# 1_MC_Peripherals.net
KiCad netlist of a schematic drawn in Altium Designer
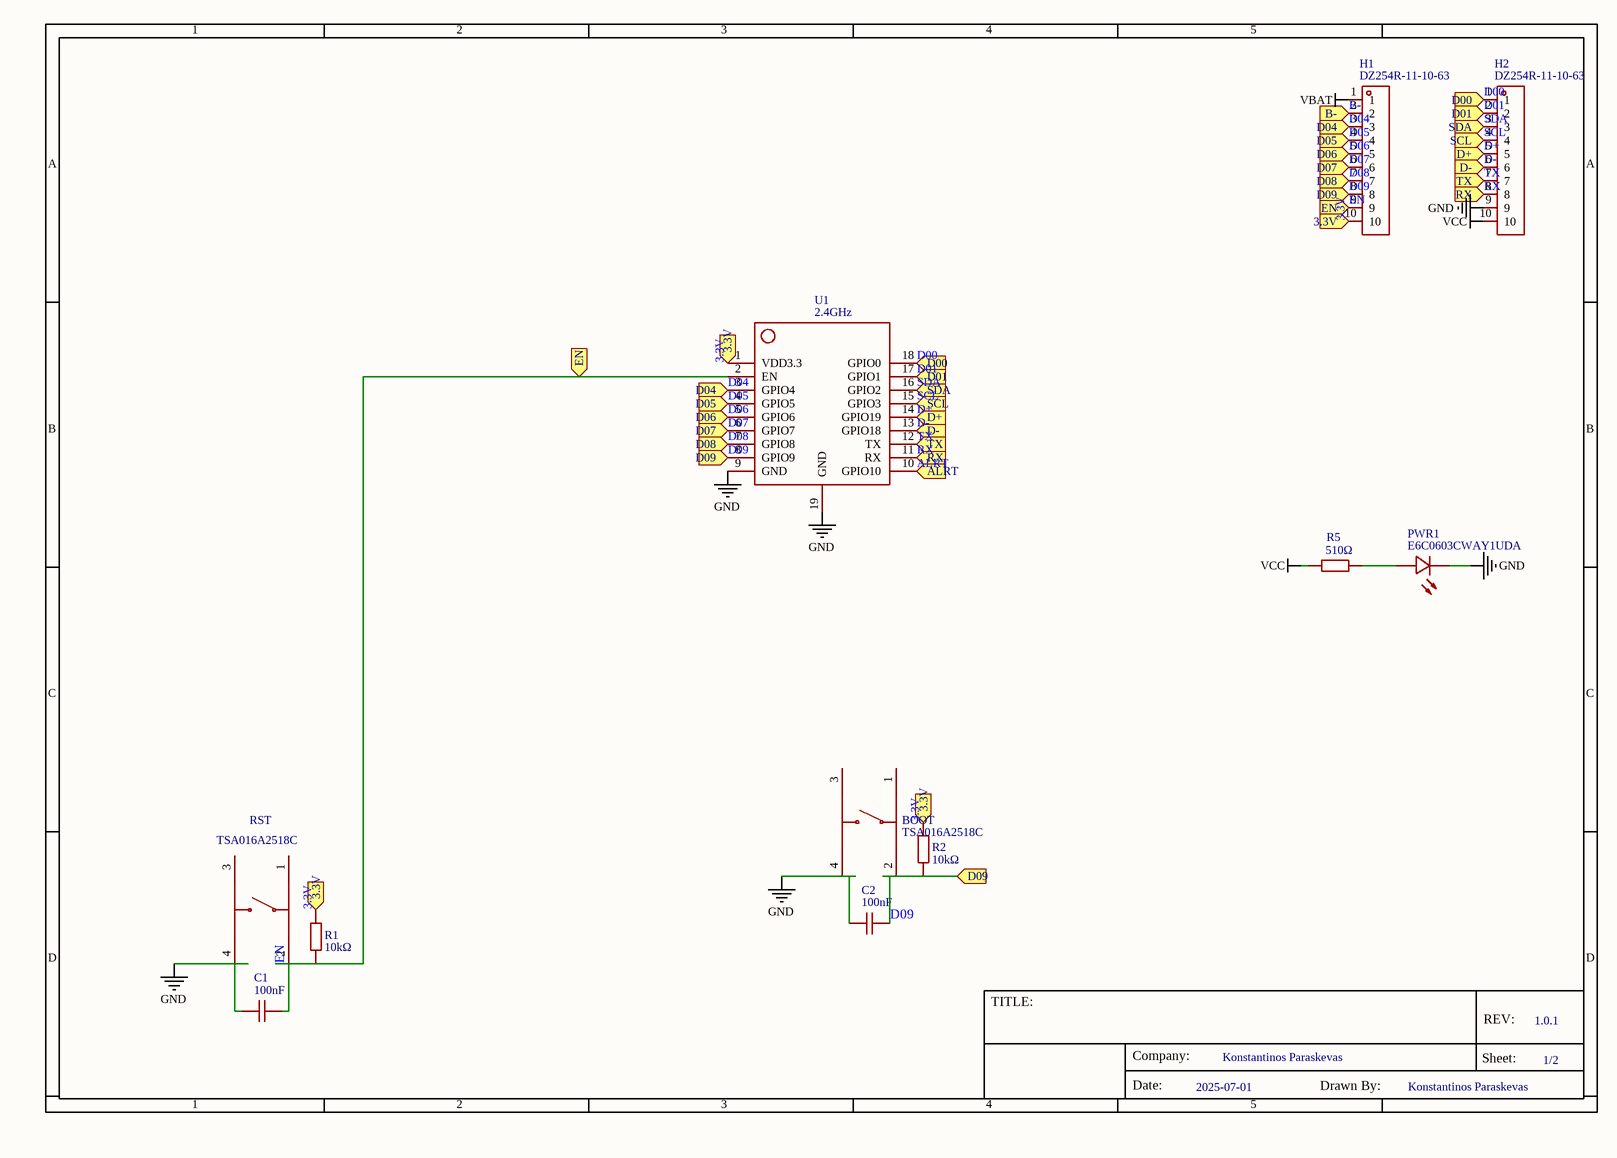
[diagram p0: 1_MC & Peripherals.schdoc]

(export (version "E")
  (design (tool "Eeschema 10.0.6"))
  (components
    (comp (ref "BOOT")
      (value "TSA016A2518C")
      (footprint "SW-SMD_4P-L4.2-W3.3-P2.15-LS4.6")
      (fields (field (name "MANUFACTURER") "BZCN(博众电气)"))
      (libsource (lib "altium-import") (part "root_3_TSA016A2518C_"))
    )
    (comp (ref "C1")
      (value "100nF")
      (footprint "C0402")
      (fields
        (field (name "MANUFACTURER") "FH(风华)")
        (field (name "MANUFACTURER PART") "0402B104K160NT")
        (field (name "TOLERANCE") "±10%")
      )
      (libsource (lib "altium-import") (part "root_0_0402B104K160NT_"))
    )
    (comp (ref "C2")
      (value "100nF")
      (footprint "C0402")
      (fields
        (field (name "MANUFACTURER") "FH(风华)")
        (field (name "MANUFACTURER PART") "0402B104K160NT")
        (field (name "TOLERANCE") "±10%")
      )
      (libsource (lib "altium-import") (part "root_0_0402B104K160NT_"))
    )
    (comp (ref "H1")
      (value "DZ254R-11-10-63")
      (footprint "HDR-TH_10P-P2.54-V-M")
      (fields (field (name "MANUFACTURER") "DEALON(德艺隆)"))
      (libsource (lib "altium-import") (part "root_0_DZ254R-11-10-63_"))
    )
    (comp (ref "H2")
      (value "DZ254R-11-10-63")
      (footprint "HDR-TH_10P-P2.54-V-M")
      (fields (field (name "MANUFACTURER") "DEALON(德艺隆)"))
      (libsource (lib "altium-import") (part "root_0_DZ254R-11-10-63_"))
    )
    (comp (ref "PWR1")
      (value "E6C0603CWAY1UDA")
      (footprint "LED0603-R-RD_WHITE")
      (fields (field (name "MANUFACTURER") "ekinglux(亿晶源)"))
      (libsource (lib "altium-import") (part "root_2_E6C0603CWAY1UDA_"))
    )
    (comp (ref "R1")
      (value "10kΩ")
      (footprint "R0402")
      (fields
        (field (name "MANUFACTURER") "大毅科技")
        (field (name "MANUFACTURER PART") "RMS04FT1002")
        (field (name "TOLERANCE") "±1%")
      )
      (libsource (lib "altium-import") (part "root_1_RMS04FT1002_"))
    )
    (comp (ref "R2")
      (value "10kΩ")
      (footprint "R0402")
      (fields
        (field (name "MANUFACTURER") "大毅科技")
        (field (name "MANUFACTURER PART") "RMS04FT1002")
        (field (name "TOLERANCE") "±1%")
      )
      (libsource (lib "altium-import") (part "root_1_RMS04FT1002_"))
    )
    (comp (ref "R5")
      (value "510Ω")
      (footprint "R0402")
      (fields
        (field (name "MANUFACTURER") "UNI-ROYAL(厚声)")
        (field (name "MANUFACTURER PART") "0402WGF5100TCE")
        (field (name "TOLERANCE") "±1%")
      )
      (libsource (lib "altium-import") (part "root_0_0402WGF5100TCE_"))
    )
    (comp (ref "RST")
      (value "TSA016A2518C")
      (footprint "SW-SMD_4P-L4.2-W3.3-P2.15-LS4.6")
      (fields (field (name "MANUFACTURER") "BZCN(博众电气)"))
      (libsource (lib "altium-import") (part "root_3_TSA016A2518C_"))
    )
    (comp (ref "U1")
      (value "2.4GHz")
      (footprint "BULETM-SMD_ESPRESSIF_ESP32-C3-WROOM-02-N4-4MB")
      (fields
        (field (name "MANUFACTURER") "ESPRESSIF(乐鑫)")
        (field (name "MANUFACTURER PART") "ESP32-C3-WROOM-02-N4")
      )
      (libsource (lib "altium-import") (part "root_0_ESP32-C3-WROOM-02-N4_C2934560_"))
    )
  )
  (nets
    (net (code "1") (name "/3.3V") (class "Default")
      (node (ref "H1") (pin "10") (pinfunction "10_10") (pintype "passive"))
      (node (ref "R1") (pin "2") (pinfunction "2_2") (pintype "passive"))
      (node (ref "R2") (pin "2") (pinfunction "2_2") (pintype "passive"))
      (node (ref "U1") (pin "1") (pinfunction "VDD3.3_1") (pintype "passive"))
    )
    (net (code "2") (name "/ALRT") (class "Default")
      (node (ref "U1") (pin "10") (pinfunction "GPIO10_10") (pintype "passive"))
    )
    (net (code "3") (name "/B-") (class "Default")
      (node (ref "H1") (pin "2") (pinfunction "2_2") (pintype "passive"))
    )
    (net (code "4") (name "/D+") (class "Default")
      (node (ref "H2") (pin "5") (pinfunction "5_5") (pintype "passive"))
      (node (ref "U1") (pin "14") (pinfunction "GPIO19_14") (pintype "passive"))
    )
    (net (code "5") (name "/D-") (class "Default")
      (node (ref "H2") (pin "6") (pinfunction "6_6") (pintype "passive"))
      (node (ref "U1") (pin "13") (pinfunction "GPIO18_13") (pintype "passive"))
    )
    (net (code "6") (name "/D00") (class "Default")
      (node (ref "H2") (pin "1") (pinfunction "1_1") (pintype "passive"))
      (node (ref "U1") (pin "18") (pinfunction "GPIO0_18") (pintype "passive"))
    )
    (net (code "7") (name "/D01") (class "Default")
      (node (ref "H2") (pin "2") (pinfunction "2_2") (pintype "passive"))
      (node (ref "U1") (pin "17") (pinfunction "GPIO1_17") (pintype "passive"))
    )
    (net (code "8") (name "/D04") (class "Default")
      (node (ref "H1") (pin "3") (pinfunction "3_3") (pintype "passive"))
      (node (ref "U1") (pin "3") (pinfunction "GPIO4_3") (pintype "passive"))
    )
    (net (code "9") (name "/D05") (class "Default")
      (node (ref "H1") (pin "4") (pinfunction "4_4") (pintype "passive"))
      (node (ref "U1") (pin "4") (pinfunction "GPIO5_4") (pintype "passive"))
    )
    (net (code "10") (name "/D06") (class "Default")
      (node (ref "H1") (pin "5") (pinfunction "5_5") (pintype "passive"))
      (node (ref "U1") (pin "5") (pinfunction "GPIO6_5") (pintype "passive"))
    )
    (net (code "11") (name "/D07") (class "Default")
      (node (ref "H1") (pin "6") (pinfunction "6_6") (pintype "passive"))
      (node (ref "U1") (pin "6") (pinfunction "GPIO7_6") (pintype "passive"))
    )
    (net (code "12") (name "/D08") (class "Default")
      (node (ref "H1") (pin "7") (pinfunction "7_7") (pintype "passive"))
      (node (ref "U1") (pin "7") (pinfunction "GPIO8_7") (pintype "passive"))
    )
    (net (code "13") (name "/D09") (class "Default")
      (node (ref "BOOT") (pin "2") (pinfunction "2_2") (pintype "passive"))
      (node (ref "C2") (pin "2") (pinfunction "2_2") (pintype "passive"))
      (node (ref "H1") (pin "8") (pinfunction "8_8") (pintype "passive"))
      (node (ref "R2") (pin "1") (pinfunction "1_1") (pintype "passive"))
      (node (ref "U1") (pin "8") (pinfunction "GPIO9_8") (pintype "passive"))
    )
    (net (code "14") (name "/EN") (class "Default")
      (node (ref "C1") (pin "2") (pinfunction "2_2") (pintype "passive"))
      (node (ref "H1") (pin "9") (pinfunction "9_9") (pintype "passive"))
      (node (ref "R1") (pin "1") (pinfunction "1_1") (pintype "passive"))
      (node (ref "RST") (pin "2") (pinfunction "2_2") (pintype "passive"))
      (node (ref "U1") (pin "2") (pinfunction "EN_2") (pintype "passive"))
    )
    (net (code "15") (name "/RX") (class "Default")
      (node (ref "H2") (pin "8") (pinfunction "8_8") (pintype "passive"))
      (node (ref "U1") (pin "11") (pinfunction "RX_11") (pintype "passive"))
    )
    (net (code "16") (name "/SCL") (class "Default")
      (node (ref "H2") (pin "4") (pinfunction "4_4") (pintype "passive"))
      (node (ref "U1") (pin "15") (pinfunction "GPIO3_15") (pintype "passive"))
    )
    (net (code "17") (name "/SDA") (class "Default")
      (node (ref "H2") (pin "3") (pinfunction "3_3") (pintype "passive"))
      (node (ref "U1") (pin "16") (pinfunction "GPIO2_16") (pintype "passive"))
    )
    (net (code "18") (name "/TX") (class "Default")
      (node (ref "H2") (pin "7") (pinfunction "7_7") (pintype "passive"))
      (node (ref "U1") (pin "12") (pinfunction "TX_12") (pintype "passive"))
    )
    (net (code "19") (name "GND") (class "Default")
      (node (ref "BOOT") (pin "4") (pinfunction "4_4") (pintype "passive"))
      (node (ref "C1") (pin "1") (pinfunction "1_1") (pintype "passive"))
      (node (ref "C2") (pin "1") (pinfunction "1_1") (pintype "passive"))
      (node (ref "H2") (pin "9") (pinfunction "9_9") (pintype "passive"))
      (node (ref "PWR1") (pin "2") (pinfunction "-_2") (pintype "passive"))
      (node (ref "RST") (pin "4") (pinfunction "4_4") (pintype "passive"))
      (node (ref "U1") (pin "19") (pinfunction "GND_19") (pintype "passive"))
      (node (ref "U1") (pin "9") (pinfunction "GND_9") (pintype "passive"))
    )
    (net (code "20") (name "Net-(PWR1-+)") (class "Default")
      (node (ref "PWR1") (pin "1") (pinfunction "+_1") (pintype "passive"))
      (node (ref "R5") (pin "2") (pinfunction "2_2") (pintype "passive"))
    )
    (net (code "21") (name "VBAT") (class "Default")
      (node (ref "H1") (pin "1") (pinfunction "1_1") (pintype "passive"))
    )
    (net (code "22") (name "VCC") (class "Default")
      (node (ref "H2") (pin "10") (pinfunction "10_10") (pintype "passive"))
      (node (ref "R5") (pin "1") (pinfunction "1_1") (pintype "passive"))
    )
    (net (code "23") (name "unconnected-(BOOT-Pad1)") (class "Default")
      (node (ref "BOOT") (pin "1") (pinfunction "1_1") (pintype "passive"))
    )
    (net (code "24") (name "unconnected-(BOOT-Pad3)") (class "Default")
      (node (ref "BOOT") (pin "3") (pinfunction "3_3") (pintype "passive"))
    )
    (net (code "25") (name "unconnected-(RST-Pad1)") (class "Default")
      (node (ref "RST") (pin "1") (pinfunction "1_1") (pintype "passive"))
    )
    (net (code "26") (name "unconnected-(RST-Pad3)") (class "Default")
      (node (ref "RST") (pin "3") (pinfunction "3_3") (pintype "passive"))
    )
  )
)
